# 3_MXM_Connector_1.net
KiCad netlist of a schematic drawn in Altium Designer
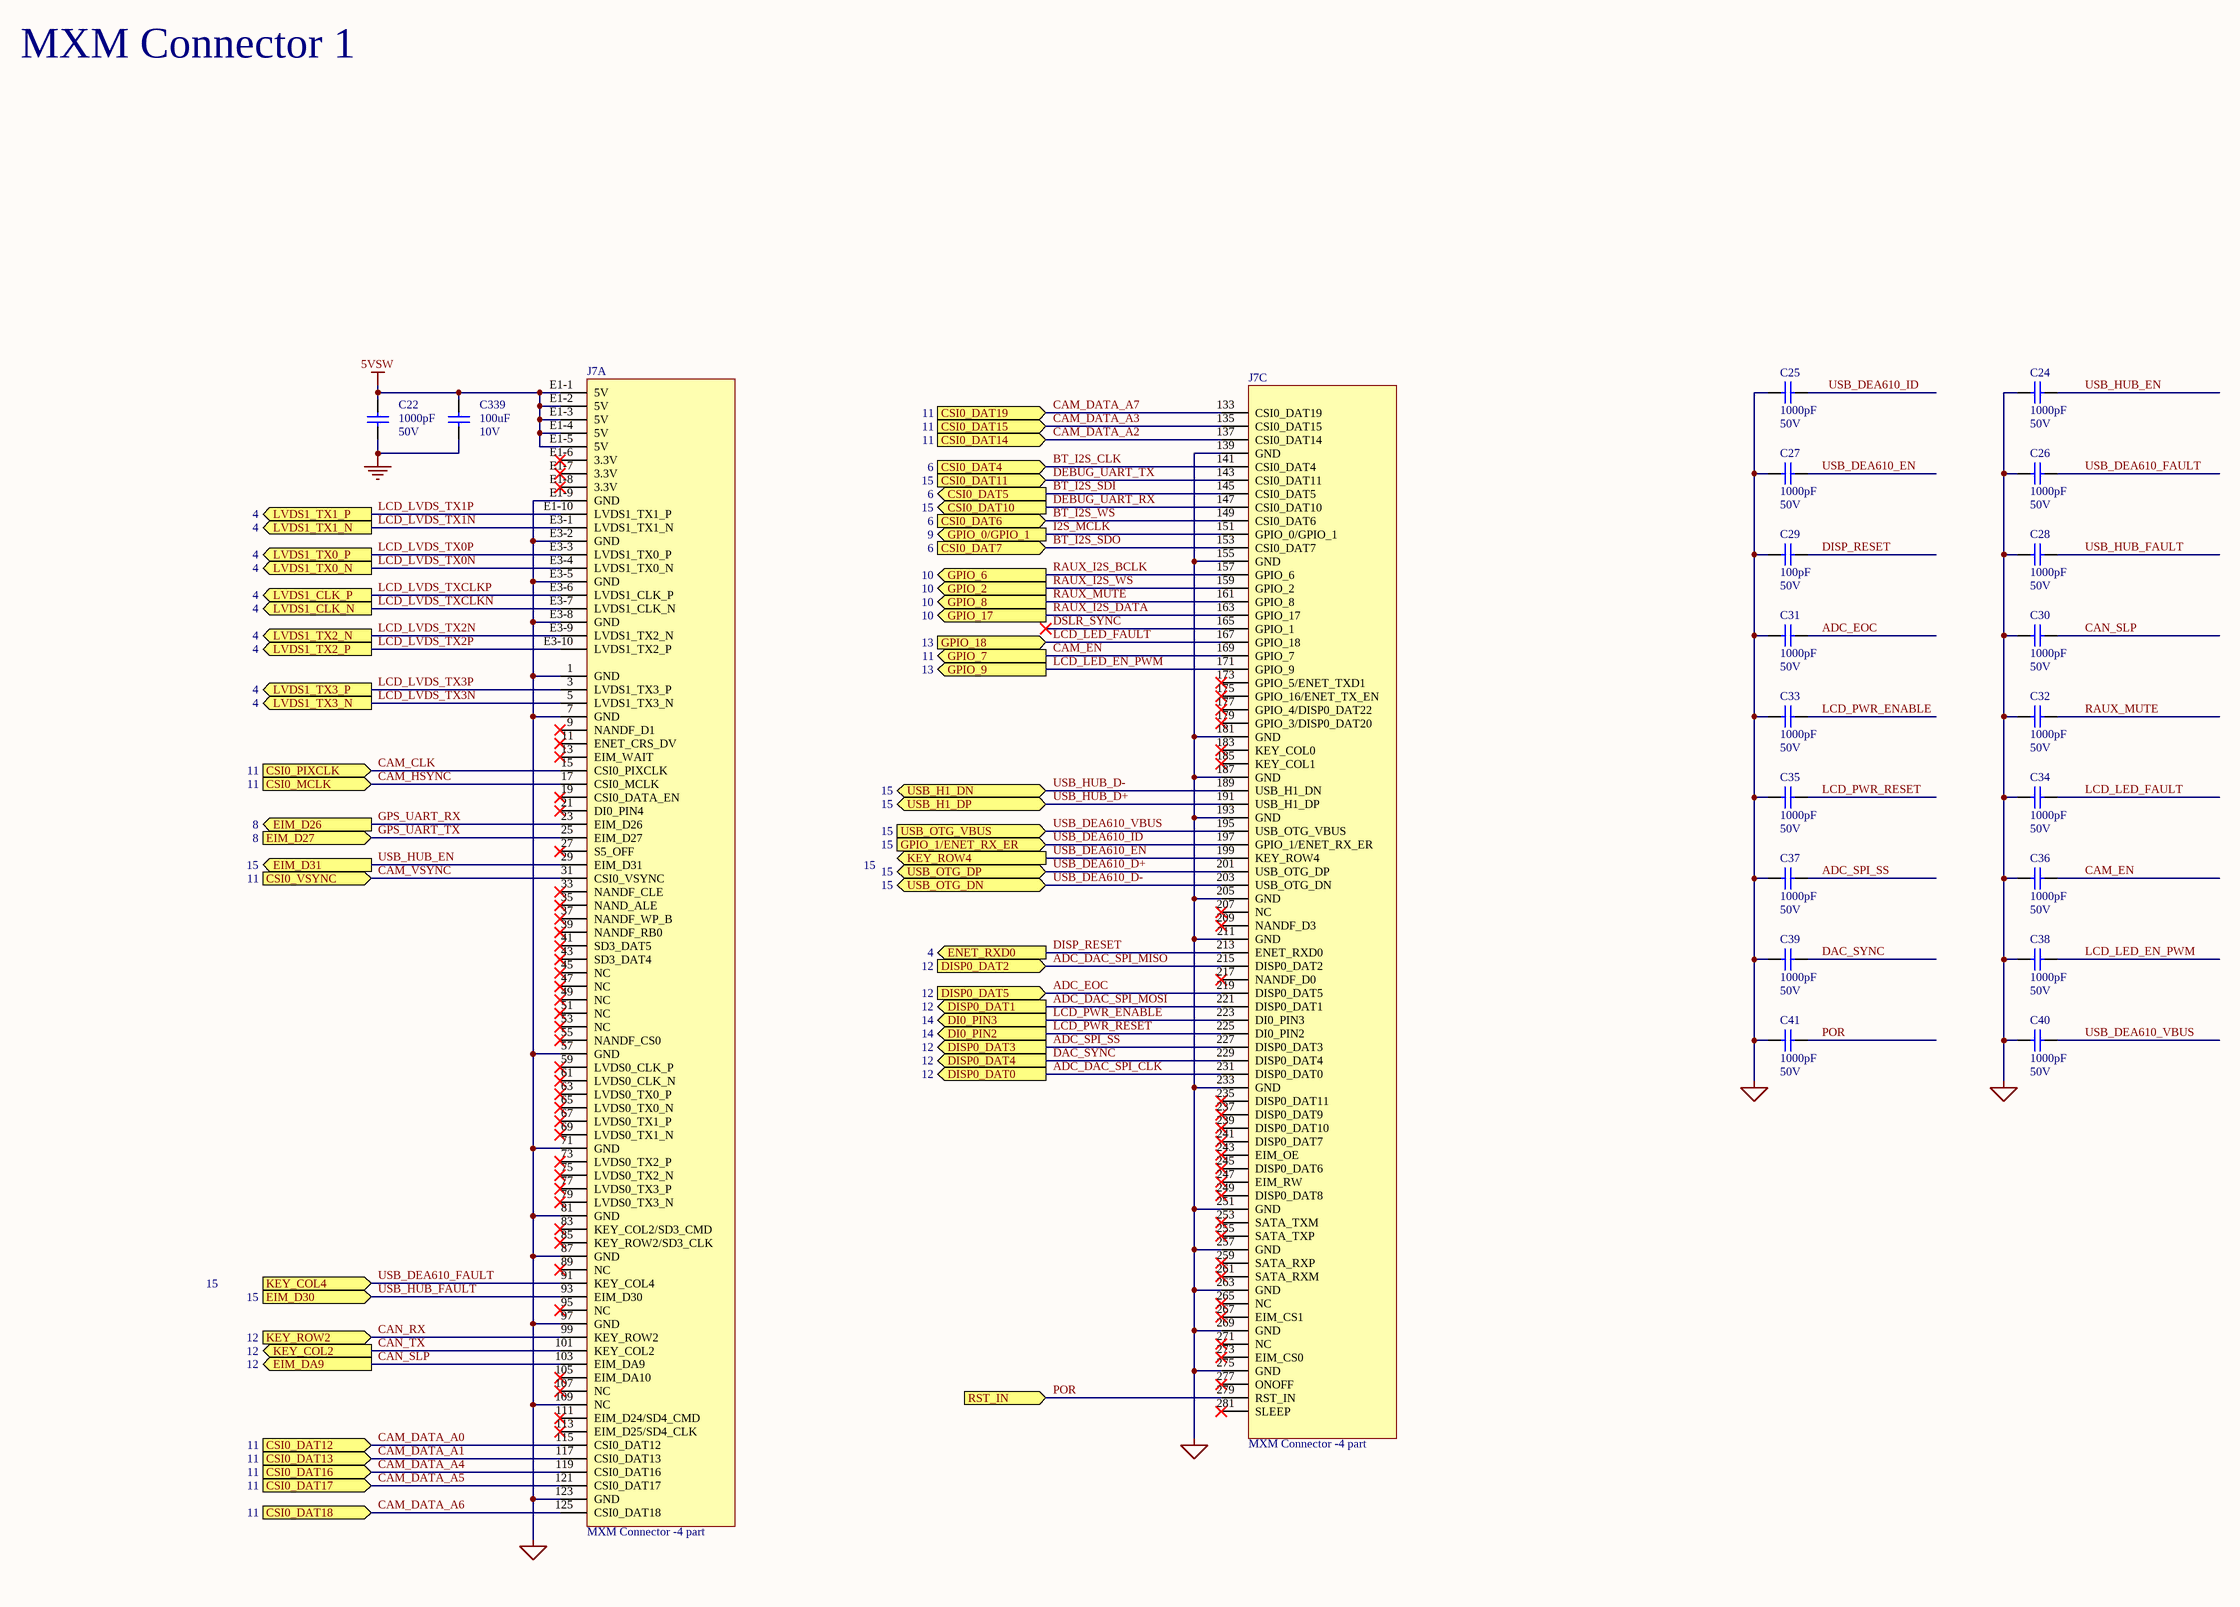
[diagram p0: 3 MXM Connector 1.SchDoc]

(export (version "E")
  (design (tool "Eeschema 10.0.6"))
  (components
    (comp (ref "C22")
      (value "1000pF")
      (footprint "CAP_0603")
      (description "Cap, Cer, 1000pF, 50V, 10%, X7S, 0603")
      (fields
        (field (name "TOLERANCE") "10%")
        (field (name "MANUFACTURER") "Yageo")
        (field (name "VOLTAGE") "50V")
      )
      (libsource (lib "Firstview") (part "Cap 1000pF 50V 0603"))
    )
    (comp (ref "C24")
      (value "1000pF")
      (footprint "CAP_0603")
      (description "Cap, Cer, 1000pF, 50V, 10%, X7S, 0603")
      (fields
        (field (name "TOLERANCE") "10%")
        (field (name "MANUFACTURER") "Yageo")
        (field (name "VOLTAGE") "50V")
      )
      (libsource (lib "Firstview") (part "Cap 1000pF 50V 0603"))
    )
    (comp (ref "C25")
      (value "1000pF")
      (footprint "CAP_0603")
      (description "Cap, Cer, 1000pF, 50V, 10%, X7S, 0603")
      (fields
        (field (name "TOLERANCE") "10%")
        (field (name "MANUFACTURER") "Yageo")
        (field (name "VOLTAGE") "50V")
      )
      (libsource (lib "Firstview") (part "Cap 1000pF 50V 0603"))
    )
    (comp (ref "C26")
      (value "1000pF")
      (footprint "CAP_0603")
      (description "Cap, Cer, 1000pF, 50V, 10%, X7S, 0603")
      (fields
        (field (name "TOLERANCE") "10%")
        (field (name "MANUFACTURER") "Yageo")
        (field (name "VOLTAGE") "50V")
      )
      (libsource (lib "Firstview") (part "Cap 1000pF 50V 0603"))
    )
    (comp (ref "C27")
      (value "1000pF")
      (footprint "CAP_0603")
      (description "Cap, Cer, 1000pF, 50V, 10%, X7S, 0603")
      (fields
        (field (name "TOLERANCE") "10%")
        (field (name "MANUFACTURER") "Yageo")
        (field (name "VOLTAGE") "50V")
      )
      (libsource (lib "Firstview") (part "Cap 1000pF 50V 0603"))
    )
    (comp (ref "C28")
      (value "1000pF")
      (footprint "CAP_0603")
      (description "Cap, Cer, 1000pF, 50V, 10%, X7S, 0603")
      (fields
        (field (name "TOLERANCE") "10%")
        (field (name "MANUFACTURER") "Yageo")
        (field (name "VOLTAGE") "50V")
      )
      (libsource (lib "Firstview") (part "Cap 1000pF 50V 0603"))
    )
    (comp (ref "C29")
      (value "100pF")
      (footprint "CAP_0402")
      (description "Cap, Cer, 100pF, 50V, 5%, C0G/NP0, 0402")
      (fields
        (field (name "TOLERANCE") "5%")
        (field (name "MANUFACTURER") "Yageo")
        (field (name "VOLTAGE") "50V")
      )
      (libsource (lib "Firstview") (part "Cap 100pF 50V 0402"))
    )
    (comp (ref "C30")
      (value "1000pF")
      (footprint "CAP_0603")
      (description "Cap, Cer, 1000pF, 50V, 10%, X7S, 0603")
      (fields
        (field (name "TOLERANCE") "10%")
        (field (name "MANUFACTURER") "Yageo")
        (field (name "VOLTAGE") "50V")
      )
      (libsource (lib "Firstview") (part "Cap 1000pF 50V 0603"))
    )
    (comp (ref "C31")
      (value "1000pF")
      (footprint "CAP_0603")
      (description "Cap, Cer, 1000pF, 50V, 10%, X7S, 0603")
      (fields
        (field (name "TOLERANCE") "10%")
        (field (name "MANUFACTURER") "Yageo")
        (field (name "VOLTAGE") "50V")
      )
      (libsource (lib "Firstview") (part "Cap 1000pF 50V 0603"))
    )
    (comp (ref "C32")
      (value "1000pF")
      (footprint "CAP_0603")
      (description "Cap, Cer, 1000pF, 50V, 10%, X7S, 0603")
      (fields
        (field (name "TOLERANCE") "10%")
        (field (name "MANUFACTURER") "Yageo")
        (field (name "VOLTAGE") "50V")
      )
      (libsource (lib "Firstview") (part "Cap 1000pF 50V 0603"))
    )
    (comp (ref "C33")
      (value "1000pF")
      (footprint "CAP_0603")
      (description "Cap, Cer, 1000pF, 50V, 10%, X7S, 0603")
      (fields
        (field (name "TOLERANCE") "10%")
        (field (name "MANUFACTURER") "Yageo")
        (field (name "VOLTAGE") "50V")
      )
      (libsource (lib "Firstview") (part "Cap 1000pF 50V 0603"))
    )
    (comp (ref "C34")
      (value "1000pF")
      (footprint "CAP_0603")
      (description "Cap, Cer, 1000pF, 50V, 10%, X7S, 0603")
      (fields
        (field (name "TOLERANCE") "10%")
        (field (name "MANUFACTURER") "Yageo")
        (field (name "VOLTAGE") "50V")
      )
      (libsource (lib "Firstview") (part "Cap 1000pF 50V 0603"))
    )
    (comp (ref "C35")
      (value "1000pF")
      (footprint "CAP_0603")
      (description "Cap, Cer, 1000pF, 50V, 10%, X7S, 0603")
      (fields
        (field (name "TOLERANCE") "10%")
        (field (name "MANUFACTURER") "Yageo")
        (field (name "VOLTAGE") "50V")
      )
      (libsource (lib "Firstview") (part "Cap 1000pF 50V 0603"))
    )
    (comp (ref "C36")
      (value "1000pF")
      (footprint "CAP_0603")
      (description "Cap, Cer, 1000pF, 50V, 10%, X7S, 0603")
      (fields
        (field (name "TOLERANCE") "10%")
        (field (name "MANUFACTURER") "Yageo")
        (field (name "VOLTAGE") "50V")
      )
      (libsource (lib "Firstview") (part "Cap 1000pF 50V 0603"))
    )
    (comp (ref "C37")
      (value "1000pF")
      (footprint "CAP_0603")
      (description "Cap, Cer, 1000pF, 50V, 10%, X7S, 0603")
      (fields
        (field (name "TOLERANCE") "10%")
        (field (name "MANUFACTURER") "Yageo")
        (field (name "VOLTAGE") "50V")
      )
      (libsource (lib "Firstview") (part "Cap 1000pF 50V 0603"))
    )
    (comp (ref "C38")
      (value "1000pF")
      (footprint "CAP_0603")
      (description "Cap, Cer, 1000pF, 50V, 10%, X7S, 0603")
      (fields
        (field (name "TOLERANCE") "10%")
        (field (name "MANUFACTURER") "Yageo")
        (field (name "VOLTAGE") "50V")
      )
      (libsource (lib "Firstview") (part "Cap 1000pF 50V 0603"))
    )
    (comp (ref "C39")
      (value "1000pF")
      (footprint "CAP_0603")
      (description "Cap, Cer, 1000pF, 50V, 10%, X7S, 0603")
      (fields
        (field (name "TOLERANCE") "10%")
        (field (name "MANUFACTURER") "Yageo")
        (field (name "VOLTAGE") "50V")
      )
      (libsource (lib "Firstview") (part "Cap 1000pF 50V 0603"))
    )
    (comp (ref "C40")
      (value "1000pF")
      (footprint "CAP_0603")
      (description "Cap, Cer, 1000pF, 50V, 10%, X7S, 0603")
      (fields
        (field (name "TOLERANCE") "10%")
        (field (name "MANUFACTURER") "Yageo")
        (field (name "VOLTAGE") "50V")
      )
      (libsource (lib "Firstview") (part "Cap 1000pF 50V 0603"))
    )
    (comp (ref "C41")
      (value "1000pF")
      (footprint "CAP_0603")
      (description "Cap, Cer, 1000pF, 50V, 10%, X7S, 0603")
      (fields
        (field (name "TOLERANCE") "10%")
        (field (name "MANUFACTURER") "Yageo")
        (field (name "VOLTAGE") "50V")
      )
      (libsource (lib "Firstview") (part "Cap 1000pF 50V 0603"))
    )
    (comp (ref "C339")
      (value "100uF")
      (footprint "CAP_1210")
      (description "Cap, Cer, 100uF, 10V, 20%, X5R, 1210")
      (fields
        (field (name "MANUFACTURER") "Kemet")
        (field (name "VOLTAGE") "10V")
        (field (name "Comment") "Cap 100uF 10V 1210")
      )
      (libsource (lib "Firstview") (part "Cap 100uF 10V 1210"))
    )
    (comp (ref "J7")
      (value "MXM Connector -4 part")
      (footprint "CON_CLE9990-0402F")
      (description "Conn, 314-pin, SOM i.MX6, SMD")
      (fields (field (name "MANUFACTURER") "SMK Electronics"))
      (libsource (lib "Firstview") (part "MXM Connector -4 part"))
    )
  )
  (nets
    (net (code "1") (name "/ADC_DAC_SPI_CLK") (class "Default")
      (node (ref "J7") (pin "231") (pinfunction "DISP0_DAT0_231") (pintype "passive"))
    )
    (net (code "2") (name "/ADC_DAC_SPI_MISO") (class "Default")
      (node (ref "J7") (pin "215") (pinfunction "DISP0_DAT2_215") (pintype "passive"))
    )
    (net (code "3") (name "/ADC_DAC_SPI_MOSI") (class "Default")
      (node (ref "J7") (pin "221") (pinfunction "DISP0_DAT1_221") (pintype "passive"))
    )
    (net (code "4") (name "/ADC_EOC") (class "Default")
      (node (ref "C31") (pin "1") (pinfunction "1_1") (pintype "passive"))
      (node (ref "J7") (pin "219") (pinfunction "DISP0_DAT5_219") (pintype "passive"))
    )
    (net (code "5") (name "/ADC_SPI_SS") (class "Default")
      (node (ref "C37") (pin "1") (pinfunction "1_1") (pintype "passive"))
      (node (ref "J7") (pin "227") (pinfunction "DISP0_DAT3_227") (pintype "passive"))
    )
    (net (code "6") (name "/BT_I2S_CLK") (class "Default")
      (node (ref "J7") (pin "141") (pinfunction "CSI0_DAT4_141") (pintype "passive"))
    )
    (net (code "7") (name "/BT_I2S_SDI") (class "Default")
      (node (ref "J7") (pin "145") (pinfunction "CSI0_DAT5_145") (pintype "passive"))
    )
    (net (code "8") (name "/BT_I2S_SDO") (class "Default")
      (node (ref "J7") (pin "153") (pinfunction "CSI0_DAT7_153") (pintype "passive"))
    )
    (net (code "9") (name "/BT_I2S_WS") (class "Default")
      (node (ref "J7") (pin "149") (pinfunction "CSI0_DAT6_149") (pintype "passive"))
    )
    (net (code "10") (name "/CAM_CLK") (class "Default")
      (node (ref "J7") (pin "15") (pinfunction "CSI0_PIXCLK_15") (pintype "passive"))
    )
    (net (code "11") (name "/CAM_DATA_A0") (class "Default")
      (node (ref "J7") (pin "115") (pinfunction "CSI0_DAT12_115") (pintype "passive"))
    )
    (net (code "12") (name "/CAM_DATA_A1") (class "Default")
      (node (ref "J7") (pin "117") (pinfunction "CSI0_DAT13_117") (pintype "passive"))
    )
    (net (code "13") (name "/CAM_DATA_A2") (class "Default")
      (node (ref "J7") (pin "137") (pinfunction "CSI0_DAT14_137") (pintype "passive"))
    )
    (net (code "14") (name "/CAM_DATA_A3") (class "Default")
      (node (ref "J7") (pin "135") (pinfunction "CSI0_DAT15_135") (pintype "passive"))
    )
    (net (code "15") (name "/CAM_DATA_A4") (class "Default")
      (node (ref "J7") (pin "119") (pinfunction "CSI0_DAT16_119") (pintype "passive"))
    )
    (net (code "16") (name "/CAM_DATA_A5") (class "Default")
      (node (ref "J7") (pin "121") (pinfunction "CSI0_DAT17_121") (pintype "passive"))
    )
    (net (code "17") (name "/CAM_DATA_A6") (class "Default")
      (node (ref "J7") (pin "125") (pinfunction "CSI0_DAT18_125") (pintype "passive"))
    )
    (net (code "18") (name "/CAM_DATA_A7") (class "Default")
      (node (ref "J7") (pin "133") (pinfunction "CSI0_DAT19_133") (pintype "passive"))
    )
    (net (code "19") (name "/CAM_EN") (class "Default")
      (node (ref "C36") (pin "1") (pinfunction "1_1") (pintype "passive"))
      (node (ref "J7") (pin "169") (pinfunction "GPIO_7_169") (pintype "passive"))
    )
    (net (code "20") (name "/CAM_HSYNC") (class "Default")
      (node (ref "J7") (pin "17") (pinfunction "CSI0_MCLK_17") (pintype "passive"))
    )
    (net (code "21") (name "/CAM_VSYNC") (class "Default")
      (node (ref "J7") (pin "31") (pinfunction "CSI0_VSYNC_31") (pintype "passive"))
    )
    (net (code "22") (name "/CAN_RX") (class "Default")
      (node (ref "J7") (pin "99") (pinfunction "KEY_ROW2_99") (pintype "passive"))
    )
    (net (code "23") (name "/CAN_SLP") (class "Default")
      (node (ref "C30") (pin "1") (pinfunction "1_1") (pintype "passive"))
      (node (ref "J7") (pin "103") (pinfunction "EIM_DA9_103") (pintype "passive"))
    )
    (net (code "24") (name "/CAN_TX") (class "Default")
      (node (ref "J7") (pin "101") (pinfunction "KEY_COL2_101") (pintype "passive"))
    )
    (net (code "25") (name "/DAC_SYNC") (class "Default")
      (node (ref "C39") (pin "1") (pinfunction "1_1") (pintype "passive"))
      (node (ref "J7") (pin "229") (pinfunction "DISP0_DAT4_229") (pintype "passive"))
    )
    (net (code "26") (name "/DEBUG_UART_RX") (class "Default")
      (node (ref "J7") (pin "147") (pinfunction "CSI0_DAT10_147") (pintype "passive"))
    )
    (net (code "27") (name "/DEBUG_UART_TX") (class "Default")
      (node (ref "J7") (pin "143") (pinfunction "CSI0_DAT11_143") (pintype "passive"))
    )
    (net (code "28") (name "/DISP_RESET") (class "Default")
      (node (ref "C29") (pin "1") (pinfunction "1_1") (pintype "passive"))
      (node (ref "J7") (pin "213") (pinfunction "ENET_RXD0_213") (pintype "passive"))
    )
    (net (code "29") (name "/DSLR_SYNC") (class "Default")
      (node (ref "J7") (pin "165") (pinfunction "GPIO_1_165") (pintype "passive+no_connect"))
    )
    (net (code "30") (name "/GPS_UART_RX") (class "Default")
      (node (ref "J7") (pin "23") (pinfunction "EIM_D26_23") (pintype "passive"))
    )
    (net (code "31") (name "/GPS_UART_TX") (class "Default")
      (node (ref "J7") (pin "25") (pinfunction "EIM_D27_25") (pintype "passive"))
    )
    (net (code "32") (name "/I2S_MCLK") (class "Default")
      (node (ref "J7") (pin "151") (pinfunction "GPIO_0/GPIO_1_151") (pintype "passive"))
    )
    (net (code "33") (name "/LCD_LED_EN_PWM") (class "Default")
      (node (ref "C38") (pin "1") (pinfunction "1_1") (pintype "passive"))
      (node (ref "J7") (pin "171") (pinfunction "GPIO_9_171") (pintype "passive"))
    )
    (net (code "34") (name "/LCD_LED_FAULT") (class "Default")
      (node (ref "C34") (pin "1") (pinfunction "1_1") (pintype "passive"))
      (node (ref "J7") (pin "167") (pinfunction "GPIO_18_167") (pintype "passive"))
    )
    (net (code "35") (name "/LCD_LVDS_TX0N") (class "Default")
      (node (ref "J7") (pin "E3-4") (pinfunction "LVDS1_TX0_N_E3-4") (pintype "passive"))
    )
    (net (code "36") (name "/LCD_LVDS_TX0P") (class "Default")
      (node (ref "J7") (pin "E3-3") (pinfunction "LVDS1_TX0_P_E3-3") (pintype "passive"))
    )
    (net (code "37") (name "/LCD_LVDS_TX1N") (class "Default")
      (node (ref "J7") (pin "E3-1") (pinfunction "LVDS1_TX1_N_E3-1") (pintype "passive"))
    )
    (net (code "38") (name "/LCD_LVDS_TX1P") (class "Default")
      (node (ref "J7") (pin "E1-10") (pinfunction "LVDS1_TX1_P_E1-10") (pintype "passive"))
    )
    (net (code "39") (name "/LCD_LVDS_TX2N") (class "Default")
      (node (ref "J7") (pin "E3-9") (pinfunction "LVDS1_TX2_N_E3-9") (pintype "passive"))
    )
    (net (code "40") (name "/LCD_LVDS_TX2P") (class "Default")
      (node (ref "J7") (pin "E3-10") (pinfunction "LVDS1_TX2_P_E3-10") (pintype "passive"))
    )
    (net (code "41") (name "/LCD_LVDS_TX3N") (class "Default")
      (node (ref "J7") (pin "5") (pinfunction "LVDS1_TX3_N_5") (pintype "passive"))
    )
    (net (code "42") (name "/LCD_LVDS_TX3P") (class "Default")
      (node (ref "J7") (pin "3") (pinfunction "LVDS1_TX3_P_3") (pintype "passive"))
    )
    (net (code "43") (name "/LCD_LVDS_TXCLKN") (class "Default")
      (node (ref "J7") (pin "E3-7") (pinfunction "LVDS1_CLK_N_E3-7") (pintype "passive"))
    )
    (net (code "44") (name "/LCD_LVDS_TXCLKP") (class "Default")
      (node (ref "J7") (pin "E3-6") (pinfunction "LVDS1_CLK_P_E3-6") (pintype "passive"))
    )
    (net (code "45") (name "/LCD_PWR_ENABLE") (class "Default")
      (node (ref "C33") (pin "1") (pinfunction "1_1") (pintype "passive"))
      (node (ref "J7") (pin "223") (pinfunction "DI0_PIN3_223") (pintype "passive"))
    )
    (net (code "46") (name "/LCD_PWR_RESET") (class "Default")
      (node (ref "C35") (pin "1") (pinfunction "1_1") (pintype "passive"))
      (node (ref "J7") (pin "225") (pinfunction "DI0_PIN2_225") (pintype "passive"))
    )
    (net (code "47") (name "/POR") (class "Default")
      (node (ref "C41") (pin "1") (pinfunction "1_1") (pintype "passive"))
      (node (ref "J7") (pin "279") (pinfunction "RST_IN_279") (pintype "passive"))
    )
    (net (code "48") (name "/RAUX_I2S_BCLK") (class "Default")
      (node (ref "J7") (pin "157") (pinfunction "GPIO_6_157") (pintype "passive"))
    )
    (net (code "49") (name "/RAUX_I2S_DATA") (class "Default")
      (node (ref "J7") (pin "163") (pinfunction "GPIO_17_163") (pintype "passive"))
    )
    (net (code "50") (name "/RAUX_I2S_WS") (class "Default")
      (node (ref "J7") (pin "159") (pinfunction "GPIO_2_159") (pintype "passive"))
    )
    (net (code "51") (name "/RAUX_MUTE") (class "Default")
      (node (ref "C32") (pin "1") (pinfunction "1_1") (pintype "passive"))
      (node (ref "J7") (pin "161") (pinfunction "GPIO_8_161") (pintype "passive"))
    )
    (net (code "52") (name "/USB_DEA610_D+") (class "Default")
      (node (ref "J7") (pin "201") (pinfunction "USB_OTG_DP_201") (pintype "passive"))
    )
    (net (code "53") (name "/USB_DEA610_D-") (class "Default")
      (node (ref "J7") (pin "203") (pinfunction "USB_OTG_DN_203") (pintype "passive"))
    )
    (net (code "54") (name "/USB_DEA610_EN") (class "Default")
      (node (ref "C27") (pin "1") (pinfunction "1_1") (pintype "passive"))
      (node (ref "J7") (pin "199") (pinfunction "KEY_ROW4_199") (pintype "passive"))
    )
    (net (code "55") (name "/USB_DEA610_FAULT") (class "Default")
      (node (ref "C26") (pin "1") (pinfunction "1_1") (pintype "passive"))
      (node (ref "J7") (pin "91") (pinfunction "KEY_COL4_91") (pintype "passive"))
    )
    (net (code "56") (name "/USB_DEA610_ID") (class "Default")
      (node (ref "C25") (pin "1") (pinfunction "1_1") (pintype "passive"))
      (node (ref "J7") (pin "197") (pinfunction "GPIO_1/ENET_RX_ER_197") (pintype "passive"))
    )
    (net (code "57") (name "/USB_DEA610_VBUS") (class "Default")
      (node (ref "C40") (pin "1") (pinfunction "1_1") (pintype "passive"))
      (node (ref "J7") (pin "195") (pinfunction "USB_OTG_VBUS_195") (pintype "passive"))
    )
    (net (code "58") (name "/USB_HUB_D+") (class "Default")
      (node (ref "J7") (pin "191") (pinfunction "USB_H1_DP_191") (pintype "passive"))
    )
    (net (code "59") (name "/USB_HUB_D-") (class "Default")
      (node (ref "J7") (pin "189") (pinfunction "USB_H1_DN_189") (pintype "passive"))
    )
    (net (code "60") (name "/USB_HUB_EN") (class "Default")
      (node (ref "C24") (pin "1") (pinfunction "1_1") (pintype "passive"))
      (node (ref "J7") (pin "29") (pinfunction "EIM_D31_29") (pintype "passive"))
    )
    (net (code "61") (name "/USB_HUB_FAULT") (class "Default")
      (node (ref "C28") (pin "1") (pinfunction "1_1") (pintype "passive"))
      (node (ref "J7") (pin "93") (pinfunction "EIM_D30_93") (pintype "passive"))
    )
    (net (code "62") (name "5VSW") (class "Default")
      (node (ref "C22") (pin "1") (pinfunction "1_1") (pintype "passive"))
      (node (ref "C339") (pin "1") (pinfunction "1_1") (pintype "passive"))
      (node (ref "J7") (pin "E1-1") (pinfunction "5V_E1-1") (pintype "passive"))
      (node (ref "J7") (pin "E1-2") (pinfunction "5V_E1-2") (pintype "passive"))
      (node (ref "J7") (pin "E1-3") (pinfunction "5V_E1-3") (pintype "passive"))
      (node (ref "J7") (pin "E1-4") (pinfunction "5V_E1-4") (pintype "passive"))
      (node (ref "J7") (pin "E1-5") (pinfunction "5V_E1-5") (pintype "passive"))
    )
    (net (code "63") (name "GND") (class "Default")
      (node (ref "C22") (pin "2") (pinfunction "2_2") (pintype "passive"))
      (node (ref "C24") (pin "2") (pinfunction "2_2") (pintype "passive"))
      (node (ref "C25") (pin "2") (pinfunction "2_2") (pintype "passive"))
      (node (ref "C26") (pin "2") (pinfunction "2_2") (pintype "passive"))
      (node (ref "C27") (pin "2") (pinfunction "2_2") (pintype "passive"))
      (node (ref "C28") (pin "2") (pinfunction "2_2") (pintype "passive"))
      (node (ref "C29") (pin "2") (pinfunction "2_2") (pintype "passive"))
      (node (ref "C30") (pin "2") (pinfunction "2_2") (pintype "passive"))
      (node (ref "C31") (pin "2") (pinfunction "2_2") (pintype "passive"))
      (node (ref "C32") (pin "2") (pinfunction "2_2") (pintype "passive"))
      (node (ref "C33") (pin "2") (pinfunction "2_2") (pintype "passive"))
      (node (ref "C339") (pin "2") (pinfunction "2_2") (pintype "passive"))
      (node (ref "C34") (pin "2") (pinfunction "2_2") (pintype "passive"))
      (node (ref "C35") (pin "2") (pinfunction "2_2") (pintype "passive"))
      (node (ref "C36") (pin "2") (pinfunction "2_2") (pintype "passive"))
      (node (ref "C37") (pin "2") (pinfunction "2_2") (pintype "passive"))
      (node (ref "C38") (pin "2") (pinfunction "2_2") (pintype "passive"))
      (node (ref "C39") (pin "2") (pinfunction "2_2") (pintype "passive"))
      (node (ref "C40") (pin "2") (pinfunction "2_2") (pintype "passive"))
      (node (ref "C41") (pin "2") (pinfunction "2_2") (pintype "passive"))
      (node (ref "J7") (pin "1") (pinfunction "GND_1") (pintype "passive"))
      (node (ref "J7") (pin "109") (pinfunction "NC_109") (pintype "passive"))
      (node (ref "J7") (pin "123") (pinfunction "GND_123") (pintype "passive"))
      (node (ref "J7") (pin "139") (pinfunction "GND_139") (pintype "passive"))
      (node (ref "J7") (pin "155") (pinfunction "GND_155") (pintype "passive"))
      (node (ref "J7") (pin "181") (pinfunction "GND_181") (pintype "passive"))
      (node (ref "J7") (pin "187") (pinfunction "GND_187") (pintype "passive"))
      (node (ref "J7") (pin "193") (pinfunction "GND_193") (pintype "passive"))
      (node (ref "J7") (pin "205") (pinfunction "GND_205") (pintype "passive"))
      (node (ref "J7") (pin "211") (pinfunction "GND_211") (pintype "passive"))
      (node (ref "J7") (pin "233") (pinfunction "GND_233") (pintype "passive"))
      (node (ref "J7") (pin "251") (pinfunction "GND_251") (pintype "passive"))
      (node (ref "J7") (pin "257") (pinfunction "GND_257") (pintype "passive"))
      (node (ref "J7") (pin "263") (pinfunction "GND_263") (pintype "passive"))
      (node (ref "J7") (pin "269") (pinfunction "GND_269") (pintype "passive"))
      (node (ref "J7") (pin "275") (pinfunction "GND_275") (pintype "passive"))
      (node (ref "J7") (pin "57") (pinfunction "GND_57") (pintype "passive"))
      (node (ref "J7") (pin "7") (pinfunction "GND_7") (pintype "passive"))
      (node (ref "J7") (pin "71") (pinfunction "GND_71") (pintype "passive"))
      (node (ref "J7") (pin "81") (pinfunction "GND_81") (pintype "passive"))
      (node (ref "J7") (pin "87") (pinfunction "GND_87") (pintype "passive"))
      (node (ref "J7") (pin "97") (pinfunction "GND_97") (pintype "passive"))
      (node (ref "J7") (pin "E1-9") (pinfunction "GND_E1-9") (pintype "passive"))
      (node (ref "J7") (pin "E3-2") (pinfunction "GND_E3-2") (pintype "passive"))
      (node (ref "J7") (pin "E3-5") (pinfunction "GND_E3-5") (pintype "passive"))
      (node (ref "J7") (pin "E3-8") (pinfunction "GND_E3-8") (pintype "passive"))
    )
    (net (code "64") (name "unconnected-(J7A-3.3V-PadE1-6)") (class "Default")
      (node (ref "J7") (pin "E1-6") (pinfunction "3.3V_E1-6") (pintype "passive+no_connect"))
    )
    (net (code "65") (name "unconnected-(J7A-3.3V-PadE1-7)") (class "Default")
      (node (ref "J7") (pin "E1-7") (pinfunction "3.3V_E1-7") (pintype "passive+no_connect"))
    )
    (net (code "66") (name "unconnected-(J7A-3.3V-PadE1-8)") (class "Default")
      (node (ref "J7") (pin "E1-8") (pinfunction "3.3V_E1-8") (pintype "passive+no_connect"))
    )
    (net (code "67") (name "unconnected-(J7A-CSI0_DATA_EN-Pad19)") (class "Default")
      (node (ref "J7") (pin "19") (pinfunction "CSI0_DATA_EN_19") (pintype "passive+no_connect"))
    )
    (net (code "68") (name "unconnected-(J7A-DI0_PIN4-Pad21)") (class "Default")
      (node (ref "J7") (pin "21") (pinfunction "DI0_PIN4_21") (pintype "passive+no_connect"))
    )
    (net (code "69") (name "unconnected-(J7A-EIM_D24{slash}SD4_CMD-Pad111)") (class "Default")
      (node (ref "J7") (pin "111") (pinfunction "EIM_D24/SD4_CMD_111") (pintype "passive+no_connect"))
    )
    (net (code "70") (name "unconnected-(J7A-EIM_D25{slash}SD4_CLK-Pad113)") (class "Default")
      (node (ref "J7") (pin "113") (pinfunction "EIM_D25/SD4_CLK_113") (pintype "passive+no_connect"))
    )
    (net (code "71") (name "unconnected-(J7A-EIM_DA10-Pad105)") (class "Default")
      (node (ref "J7") (pin "105") (pinfunction "EIM_DA10_105") (pintype "passive+no_connect"))
    )
    (net (code "72") (name "unconnected-(J7A-EIM_WAIT-Pad13)") (class "Default")
      (node (ref "J7") (pin "13") (pinfunction "EIM_WAIT_13") (pintype "passive+no_connect"))
    )
    (net (code "73") (name "unconnected-(J7A-ENET_CRS_DV-Pad11)") (class "Default")
      (node (ref "J7") (pin "11") (pinfunction "ENET_CRS_DV_11") (pintype "passive+no_connect"))
    )
    (net (code "74") (name "unconnected-(J7A-KEY_COL2{slash}SD3_CMD-Pad83)") (class "Default")
      (node (ref "J7") (pin "83") (pinfunction "KEY_COL2/SD3_CMD_83") (pintype "passive+no_connect"))
    )
    (net (code "75") (name "unconnected-(J7A-KEY_ROW2{slash}SD3_CLK-Pad85)") (class "Default")
      (node (ref "J7") (pin "85") (pinfunction "KEY_ROW2/SD3_CLK_85") (pintype "passive+no_connect"))
    )
    (net (code "76") (name "unconnected-(J7A-LVDS0_CLK_N-Pad61)") (class "Default")
      (node (ref "J7") (pin "61") (pinfunction "LVDS0_CLK_N_61") (pintype "passive+no_connect"))
    )
    (net (code "77") (name "unconnected-(J7A-LVDS0_CLK_P-Pad59)") (class "Default")
      (node (ref "J7") (pin "59") (pinfunction "LVDS0_CLK_P_59") (pintype "passive+no_connect"))
    )
    (net (code "78") (name "unconnected-(J7A-LVDS0_TX0_N-Pad65)") (class "Default")
      (node (ref "J7") (pin "65") (pinfunction "LVDS0_TX0_N_65") (pintype "passive+no_connect"))
    )
    (net (code "79") (name "unconnected-(J7A-LVDS0_TX0_P-Pad63)") (class "Default")
      (node (ref "J7") (pin "63") (pinfunction "LVDS0_TX0_P_63") (pintype "passive+no_connect"))
    )
    (net (code "80") (name "unconnected-(J7A-LVDS0_TX1_N-Pad69)") (class "Default")
      (node (ref "J7") (pin "69") (pinfunction "LVDS0_TX1_N_69") (pintype "passive+no_connect"))
    )
    (net (code "81") (name "unconnected-(J7A-LVDS0_TX1_P-Pad67)") (class "Default")
      (node (ref "J7") (pin "67") (pinfunction "LVDS0_TX1_P_67") (pintype "passive+no_connect"))
    )
    (net (code "82") (name "unconnected-(J7A-LVDS0_TX2_N-Pad75)") (class "Default")
      (node (ref "J7") (pin "75") (pinfunction "LVDS0_TX2_N_75") (pintype "passive+no_connect"))
    )
    (net (code "83") (name "unconnected-(J7A-LVDS0_TX2_P-Pad73)") (class "Default")
      (node (ref "J7") (pin "73") (pinfunction "LVDS0_TX2_P_73") (pintype "passive+no_connect"))
    )
    (net (code "84") (name "unconnected-(J7A-LVDS0_TX3_N-Pad79)") (class "Default")
      (node (ref "J7") (pin "79") (pinfunction "LVDS0_TX3_N_79") (pintype "passive+no_connect"))
    )
    (net (code "85") (name "unconnected-(J7A-LVDS0_TX3_P-Pad77)") (class "Default")
      (node (ref "J7") (pin "77") (pinfunction "LVDS0_TX3_P_77") (pintype "passive+no_connect"))
    )
    (net (code "86") (name "unconnected-(J7A-NANDF_CLE-Pad33)") (class "Default")
      (node (ref "J7") (pin "33") (pinfunction "NANDF_CLE_33") (pintype "passive+no_connect"))
    )
    (net (code "87") (name "unconnected-(J7A-NANDF_CS0-Pad55)") (class "Default")
      (node (ref "J7") (pin "55") (pinfunction "NANDF_CS0_55") (pintype "passive+no_connect"))
    )
    (net (code "88") (name "unconnected-(J7A-NANDF_D1-Pad9)") (class "Default")
      (node (ref "J7") (pin "9") (pinfunction "NANDF_D1_9") (pintype "passive+no_connect"))
    )
    (net (code "89") (name "unconnected-(J7A-NANDF_RB0-Pad39)") (class "Default")
      (node (ref "J7") (pin "39") (pinfunction "NANDF_RB0_39") (pintype "passive+no_connect"))
    )
    (net (code "90") (name "unconnected-(J7A-NANDF_WP_B-Pad37)") (class "Default")
      (node (ref "J7") (pin "37") (pinfunction "NANDF_WP_B_37") (pintype "passive+no_connect"))
    )
    (net (code "91") (name "unconnected-(J7A-NAND_ALE-Pad35)") (class "Default")
      (node (ref "J7") (pin "35") (pinfunction "NAND_ALE_35") (pintype "passive+no_connect"))
    )
    (net (code "92") (name "unconnected-(J7A-NC-Pad45)") (class "Default")
      (node (ref "J7") (pin "45") (pinfunction "NC_45") (pintype "passive+no_connect"))
    )
    (net (code "93") (name "unconnected-(J7A-NC-Pad47)") (class "Default")
      (node (ref "J7") (pin "47") (pinfunction "NC_47") (pintype "passive+no_connect"))
    )
    (net (code "94") (name "unconnected-(J7A-NC-Pad49)") (class "Default")
      (node (ref "J7") (pin "49") (pinfunction "NC_49") (pintype "passive+no_connect"))
    )
    (net (code "95") (name "unconnected-(J7A-NC-Pad51)") (class "Default")
      (node (ref "J7") (pin "51") (pinfunction "NC_51") (pintype "passive+no_connect"))
    )
    (net (code "96") (name "unconnected-(J7A-NC-Pad53)") (class "Default")
      (node (ref "J7") (pin "53") (pinfunction "NC_53") (pintype "passive+no_connect"))
    )
    (net (code "97") (name "unconnected-(J7A-NC-Pad89)") (class "Default")
      (node (ref "J7") (pin "89") (pinfunction "NC_89") (pintype "passive+no_connect"))
    )
    (net (code "98") (name "unconnected-(J7A-NC-Pad95)") (class "Default")
      (node (ref "J7") (pin "95") (pinfunction "NC_95") (pintype "passive+no_connect"))
    )
    (net (code "99") (name "unconnected-(J7A-NC-Pad107)") (class "Default")
      (node (ref "J7") (pin "107") (pinfunction "NC_107") (pintype "passive+no_connect"))
    )
    (net (code "100") (name "unconnected-(J7A-S5_OFF-Pad27)") (class "Default")
      (node (ref "J7") (pin "27") (pinfunction "S5_OFF_27") (pintype "passive+no_connect"))
    )
    (net (code "101") (name "unconnected-(J7A-SD3_DAT4-Pad43)") (class "Default")
      (node (ref "J7") (pin "43") (pinfunction "SD3_DAT4_43") (pintype "passive+no_connect"))
    )
    (net (code "102") (name "unconnected-(J7A-SD3_DAT5-Pad41)") (class "Default")
      (node (ref "J7") (pin "41") (pinfunction "SD3_DAT5_41") (pintype "passive+no_connect"))
    )
    (net (code "103") (name "unconnected-(J7C-DISP0_DAT6-Pad245)") (class "Default")
      (node (ref "J7") (pin "245") (pinfunction "DISP0_DAT6_245") (pintype "passive+no_connect"))
    )
    (net (code "104") (name "unconnected-(J7C-DISP0_DAT7-Pad241)") (class "Default")
      (node (ref "J7") (pin "241") (pinfunction "DISP0_DAT7_241") (pintype "passive+no_connect"))
    )
    (net (code "105") (name "unconnected-(J7C-DISP0_DAT8-Pad249)") (class "Default")
      (node (ref "J7") (pin "249") (pinfunction "DISP0_DAT8_249") (pintype "passive+no_connect"))
    )
    (net (code "106") (name "unconnected-(J7C-DISP0_DAT9-Pad237)") (class "Default")
      (node (ref "J7") (pin "237") (pinfunction "DISP0_DAT9_237") (pintype "passive+no_connect"))
    )
    (net (code "107") (name "unconnected-(J7C-DISP0_DAT10-Pad239)") (class "Default")
      (node (ref "J7") (pin "239") (pinfunction "DISP0_DAT10_239") (pintype "passive+no_connect"))
    )
    (net (code "108") (name "unconnected-(J7C-DISP0_DAT11-Pad235)") (class "Default")
      (node (ref "J7") (pin "235") (pinfunction "DISP0_DAT11_235") (pintype "passive+no_connect"))
    )
    (net (code "109") (name "unconnected-(J7C-EIM_CS0-Pad273)") (class "Default")
      (node (ref "J7") (pin "273") (pinfunction "EIM_CS0_273") (pintype "passive+no_connect"))
    )
    (net (code "110") (name "unconnected-(J7C-EIM_CS1-Pad267)") (class "Default")
      (node (ref "J7") (pin "267") (pinfunction "EIM_CS1_267") (pintype "passive+no_connect"))
    )
    (net (code "111") (name "unconnected-(J7C-EIM_OE-Pad243)") (class "Default")
      (node (ref "J7") (pin "243") (pinfunction "EIM_OE_243") (pintype "passive+no_connect"))
    )
    (net (code "112") (name "unconnected-(J7C-EIM_RW-Pad247)") (class "Default")
      (node (ref "J7") (pin "247") (pinfunction "EIM_RW_247") (pintype "passive+no_connect"))
    )
    (net (code "113") (name "unconnected-(J7C-GPIO_3{slash}DISP0_DAT20-Pad179)") (class "Default")
      (node (ref "J7") (pin "179") (pinfunction "GPIO_3/DISP0_DAT20_179") (pintype "passive+no_connect"))
    )
    (net (code "114") (name "unconnected-(J7C-GPIO_4{slash}DISP0_DAT22-Pad177)") (class "Default")
      (node (ref "J7") (pin "177") (pinfunction "GPIO_4/DISP0_DAT22_177") (pintype "passive+no_connect"))
    )
    (net (code "115") (name "unconnected-(J7C-GPIO_5{slash}ENET_TXD1-Pad173)") (class "Default")
      (node (ref "J7") (pin "173") (pinfunction "GPIO_5/ENET_TXD1_173") (pintype "passive+no_connect"))
    )
    (net (code "116") (name "unconnected-(J7C-GPIO_16{slash}ENET_TX_EN-Pad175)") (class "Default")
      (node (ref "J7") (pin "175") (pinfunction "GPIO_16/ENET_TX_EN_175") (pintype "passive+no_connect"))
    )
    (net (code "117") (name "unconnected-(J7C-KEY_COL0-Pad183)") (class "Default")
      (node (ref "J7") (pin "183") (pinfunction "KEY_COL0_183") (pintype "passive+no_connect"))
    )
    (net (code "118") (name "unconnected-(J7C-KEY_COL1-Pad185)") (class "Default")
      (node (ref "J7") (pin "185") (pinfunction "KEY_COL1_185") (pintype "passive+no_connect"))
    )
    (net (code "119") (name "unconnected-(J7C-NANDF_D0-Pad217)") (class "Default")
      (node (ref "J7") (pin "217") (pinfunction "NANDF_D0_217") (pintype "passive+no_connect"))
    )
    (net (code "120") (name "unconnected-(J7C-NANDF_D3-Pad209)") (class "Default")
      (node (ref "J7") (pin "209") (pinfunction "NANDF_D3_209") (pintype "passive+no_connect"))
    )
    (net (code "121") (name "unconnected-(J7C-NC-Pad207)") (class "Default")
      (node (ref "J7") (pin "207") (pinfunction "NC_207") (pintype "passive+no_connect"))
    )
    (net (code "122") (name "unconnected-(J7C-NC-Pad265)") (class "Default")
      (node (ref "J7") (pin "265") (pinfunction "NC_265") (pintype "passive+no_connect"))
    )
    (net (code "123") (name "unconnected-(J7C-NC-Pad271)") (class "Default")
      (node (ref "J7") (pin "271") (pinfunction "NC_271") (pintype "passive+no_connect"))
    )
    (net (code "124") (name "unconnected-(J7C-ONOFF-Pad277)") (class "Default")
      (node (ref "J7") (pin "277") (pinfunction "ONOFF_277") (pintype "passive+no_connect"))
    )
    (net (code "125") (name "unconnected-(J7C-SATA_RXM-Pad261)") (class "Default")
      (node (ref "J7") (pin "261") (pinfunction "SATA_RXM_261") (pintype "passive+no_connect"))
    )
    (net (code "126") (name "unconnected-(J7C-SATA_RXP-Pad259)") (class "Default")
      (node (ref "J7") (pin "259") (pinfunction "SATA_RXP_259") (pintype "passive+no_connect"))
    )
    (net (code "127") (name "unconnected-(J7C-SATA_TXM-Pad253)") (class "Default")
      (node (ref "J7") (pin "253") (pinfunction "SATA_TXM_253") (pintype "passive+no_connect"))
    )
    (net (code "128") (name "unconnected-(J7C-SATA_TXP-Pad255)") (class "Default")
      (node (ref "J7") (pin "255") (pinfunction "SATA_TXP_255") (pintype "passive+no_connect"))
    )
    (net (code "129") (name "unconnected-(J7C-SLEEP-Pad281)") (class "Default")
      (node (ref "J7") (pin "281") (pinfunction "SLEEP_281") (pintype "passive+no_connect"))
    )
  )
)
